# v4smd.net
KiCad netlist of a schematic drawn in EAGLE
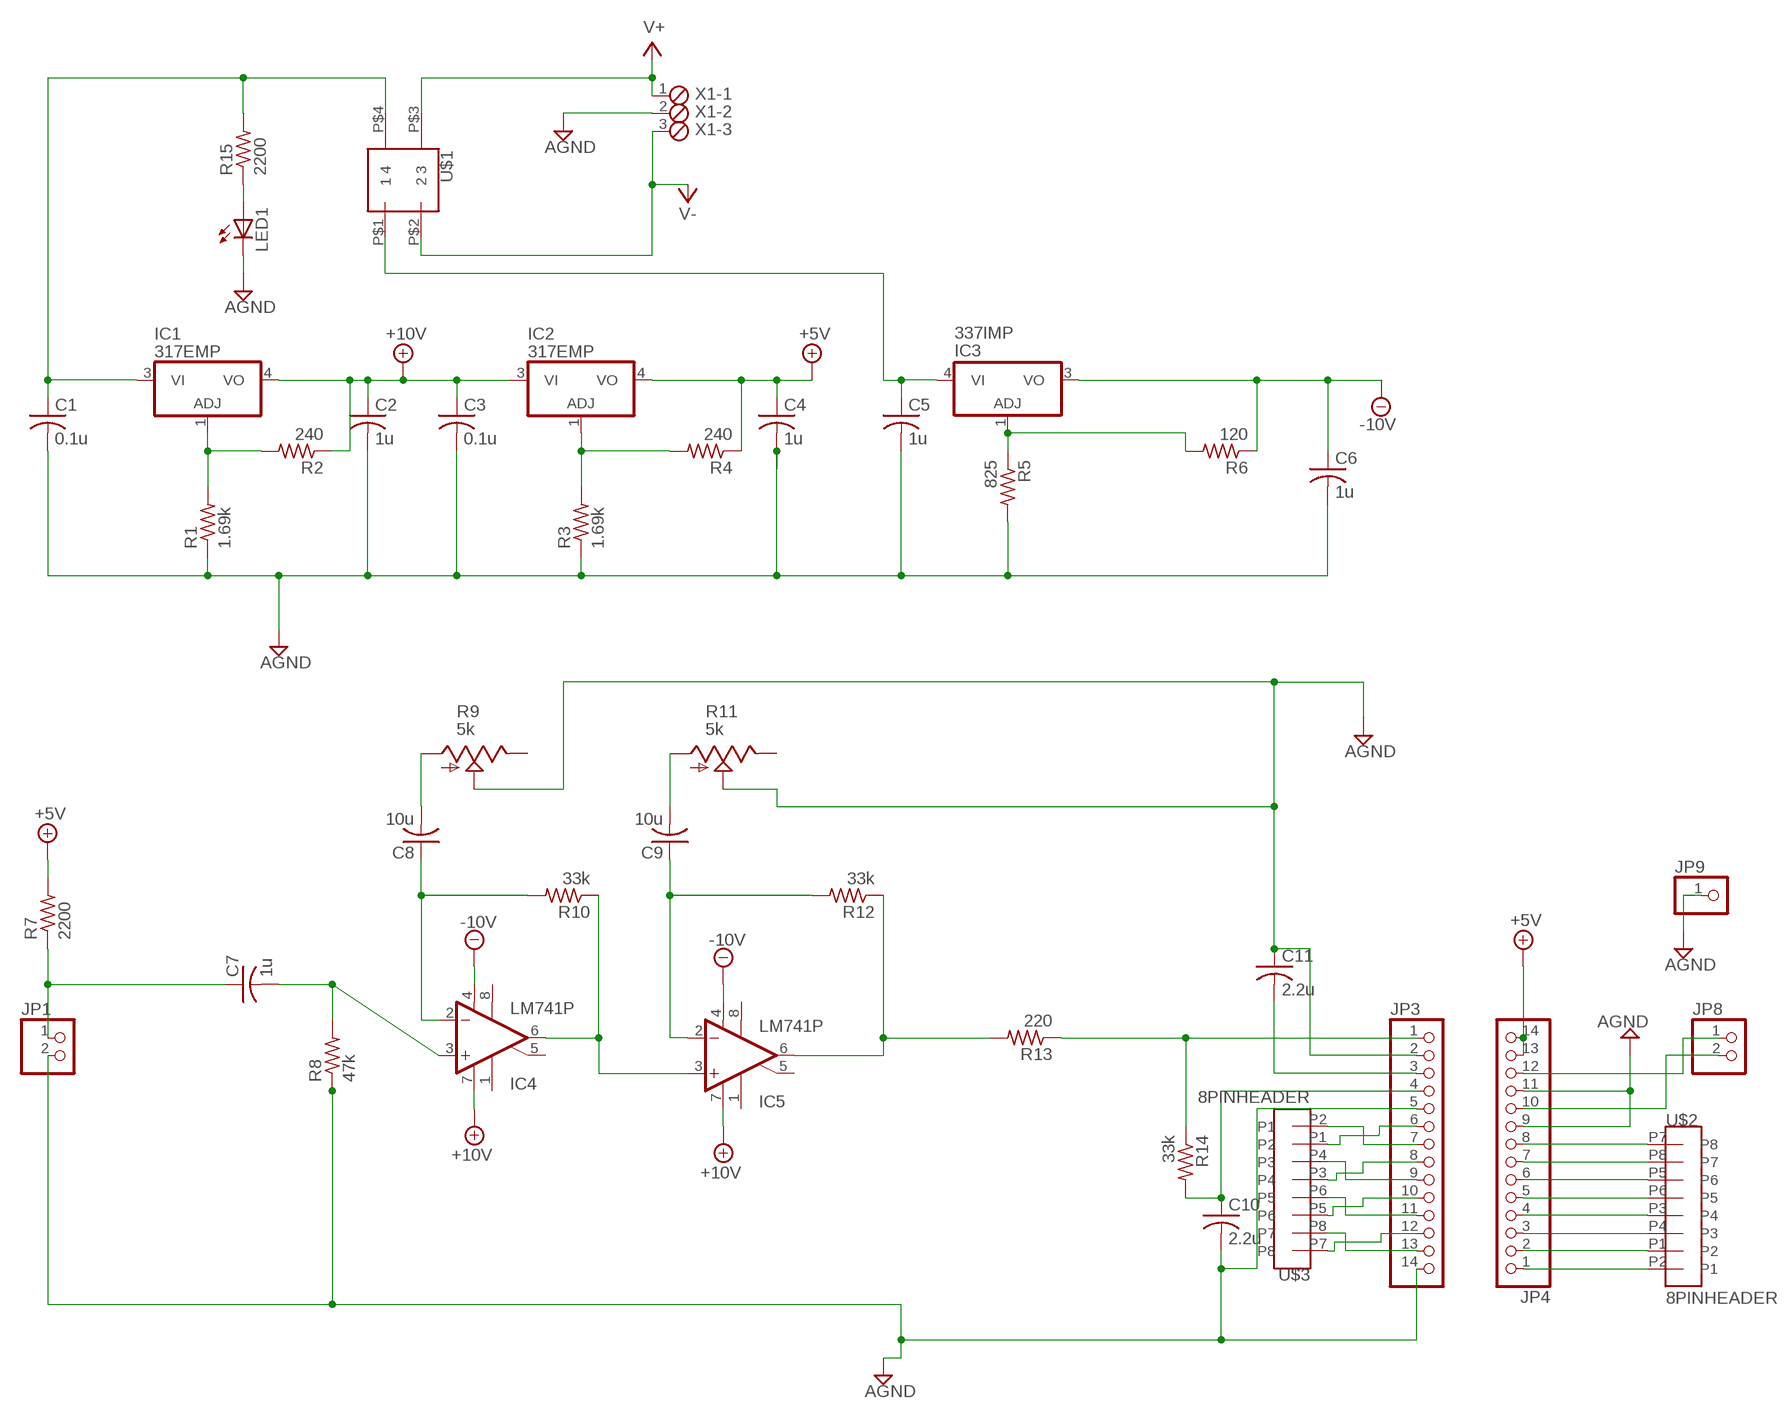
[diagram p0: schematic, sheet 1]

(export (version "E")
  (design (tool "Eeschema 10.0.6"))
  (components
    (comp (ref "C1")
      (value "0.1u")
      (footprint "eagle-import:C1206")
      (libsource (lib "eagle-import") (part "C-USC1206"))
    )
    (comp (ref "C2")
      (value "1u")
      (footprint "eagle-import:C1206")
      (libsource (lib "eagle-import") (part "C-USC1206"))
    )
    (comp (ref "C3")
      (value "0.1u")
      (footprint "eagle-import:C1206")
      (libsource (lib "eagle-import") (part "C-USC1206"))
    )
    (comp (ref "C4")
      (value "1u")
      (footprint "eagle-import:C1206")
      (libsource (lib "eagle-import") (part "C-USC1206"))
    )
    (comp (ref "C5")
      (value "1u")
      (footprint "eagle-import:C1206")
      (libsource (lib "eagle-import") (part "C-USC1206"))
    )
    (comp (ref "C6")
      (value "1u")
      (footprint "eagle-import:C1206")
      (libsource (lib "eagle-import") (part "C-USC1206"))
    )
    (comp (ref "C7")
      (value "1u")
      (footprint "eagle-import:C1206")
      (libsource (lib "eagle-import") (part "C-USC1206"))
    )
    (comp (ref "C8")
      (value "10u")
      (footprint "eagle-import:C1206")
      (libsource (lib "eagle-import") (part "C-USC1206"))
    )
    (comp (ref "C9")
      (value "10u")
      (footprint "eagle-import:C1206")
      (libsource (lib "eagle-import") (part "C-USC1206"))
    )
    (comp (ref "C10")
      (value "2.2u")
      (footprint "eagle-import:C1206")
      (libsource (lib "eagle-import") (part "C-USC1206"))
    )
    (comp (ref "C11")
      (value "2.2u")
      (footprint "eagle-import:C1206")
      (libsource (lib "eagle-import") (part "C-USC1206"))
    )
    (comp (ref "IC1")
      (value "317EMP")
      (footprint "eagle-import:SOT223")
      (libsource (lib "eagle-import") (part "317EMP"))
    )
    (comp (ref "IC2")
      (value "317EMP")
      (footprint "eagle-import:SOT223")
      (libsource (lib "eagle-import") (part "317EMP"))
    )
    (comp (ref "IC3")
      (value "337IMP")
      (footprint "eagle-import:SOT223")
      (libsource (lib "eagle-import") (part "337IMP"))
    )
    (comp (ref "IC4")
      (value "LM741P")
      (footprint "eagle-import:DIL08")
      (libsource (lib "eagle-import") (part "741PLM"))
    )
    (comp (ref "IC5")
      (value "LM741P")
      (footprint "eagle-import:DIL08")
      (libsource (lib "eagle-import") (part "741PLM"))
    )
    (comp (ref "JP1")
      (value "PINHD-1X2")
      (footprint "eagle-import:1X02")
      (libsource (lib "eagle-import") (part "PINHD-1X2"))
    )
    (comp (ref "JP3")
      (value "PINHD-1X14")
      (footprint "eagle-import:1X14")
      (libsource (lib "eagle-import") (part "PINHD-1X14"))
    )
    (comp (ref "JP4")
      (value "PINHD-1X14")
      (footprint "eagle-import:1X14")
      (libsource (lib "eagle-import") (part "PINHD-1X14"))
    )
    (comp (ref "JP8")
      (value "PINHD-1X2")
      (footprint "eagle-import:1X02")
      (libsource (lib "eagle-import") (part "PINHD-1X2"))
    )
    (comp (ref "JP9")
      (value "PINHD-1X1")
      (footprint "eagle-import:1X01")
      (libsource (lib "eagle-import") (part "PINHD-1X1"))
    )
    (comp (ref "LED1")
      (value "LED3MM")
      (footprint "eagle-import:LED3MM")
      (libsource (lib "eagle-import") (part "LED3MM"))
    )
    (comp (ref "R1")
      (value "1.69k")
      (footprint "eagle-import:R2512")
      (libsource (lib "eagle-import") (part "R-US_R2512"))
    )
    (comp (ref "R2")
      (value "240")
      (footprint "eagle-import:R2512")
      (libsource (lib "eagle-import") (part "R-US_R2512"))
    )
    (comp (ref "R3")
      (value "1.69k")
      (footprint "eagle-import:R2512")
      (libsource (lib "eagle-import") (part "R-US_R2512"))
    )
    (comp (ref "R4")
      (value "240")
      (footprint "eagle-import:R2512")
      (libsource (lib "eagle-import") (part "R-US_R2512"))
    )
    (comp (ref "R5")
      (value "825")
      (footprint "eagle-import:R2512")
      (libsource (lib "eagle-import") (part "R-US_R2512"))
    )
    (comp (ref "R6")
      (value "120")
      (footprint "eagle-import:R2512")
      (libsource (lib "eagle-import") (part "R-US_R2512"))
    )
    (comp (ref "R7")
      (value "2200")
      (footprint "eagle-import:R2512")
      (libsource (lib "eagle-import") (part "R-US_R2512"))
    )
    (comp (ref "R8")
      (value "47k")
      (footprint "eagle-import:R2512")
      (libsource (lib "eagle-import") (part "R-US_R2512"))
    )
    (comp (ref "R9")
      (value "5k")
      (footprint "eagle-import:B64Y")
      (libsource (lib "eagle-import") (part "TRIM_US-B64Y"))
    )
    (comp (ref "R10")
      (value "33k")
      (footprint "eagle-import:R2512")
      (libsource (lib "eagle-import") (part "R-US_R2512"))
    )
    (comp (ref "R11")
      (value "5k")
      (footprint "eagle-import:B64Y")
      (libsource (lib "eagle-import") (part "TRIM_US-B64Y"))
    )
    (comp (ref "R12")
      (value "33k")
      (footprint "eagle-import:R2512")
      (libsource (lib "eagle-import") (part "R-US_R2512"))
    )
    (comp (ref "R13")
      (value "220")
      (footprint "eagle-import:R2512")
      (libsource (lib "eagle-import") (part "R-US_R2512"))
    )
    (comp (ref "R14")
      (value "33k")
      (footprint "eagle-import:R2512")
      (libsource (lib "eagle-import") (part "R-US_R2512"))
    )
    (comp (ref "R15")
      (value "2200")
      (footprint "eagle-import:R2512")
      (libsource (lib "eagle-import") (part "R-US_R2512"))
    )
    (comp (ref "U$1")
      (value "S201031MS02Q")
      (footprint "eagle-import:DPST_FOOTPRINT")
      (libsource (lib "eagle-import") (part "S201031MS02Q"))
    )
    (comp (ref "U$2")
      (value "8PINHEADER")
      (footprint "eagle-import:2X4HEADER")
      (libsource (lib "eagle-import") (part "8PINHEADER"))
    )
    (comp (ref "U$3")
      (value "8PINHEADER")
      (footprint "eagle-import:2X4HEADER")
      (libsource (lib "eagle-import") (part "8PINHEADER"))
    )
    (comp (ref "X1")
      (value "MPT3")
      (footprint "eagle-import:3POL254")
      (libsource (lib "eagle-import") (part "MPT3"))
    )
  )
  (nets
    (net (code "1") (name "+5V") (class "Default")
      (node (ref "C4") (pin "1") (pinfunction "1_1") (pintype "passive"))
      (node (ref "IC2") (pin "4") (pinfunction "VO_4") (pintype "passive"))
      (node (ref "JP4") (pin "13") (pinfunction "13_13") (pintype "passive"))
      (node (ref "JP4") (pin "14") (pinfunction "14_14") (pintype "passive"))
      (node (ref "R4") (pin "1") (pinfunction "1_1") (pintype "passive"))
      (node (ref "R7") (pin "2") (pinfunction "2_2") (pintype "passive"))
    )
    (net (code "2") (name "+10V") (class "Default")
      (node (ref "C2") (pin "1") (pinfunction "1_1") (pintype "passive"))
      (node (ref "C3") (pin "1") (pinfunction "1_1") (pintype "passive"))
      (node (ref "IC1") (pin "4") (pinfunction "VO_4") (pintype "passive"))
      (node (ref "IC2") (pin "3") (pinfunction "VI_3") (pintype "input"))
      (node (ref "IC4") (pin "7") (pinfunction "V+_7") (pintype "power_in"))
      (node (ref "IC5") (pin "7") (pinfunction "V+_7") (pintype "power_in"))
      (node (ref "R2") (pin "1") (pinfunction "1_1") (pintype "passive"))
    )
    (net (code "3") (name "-10V") (class "Default")
      (node (ref "C6") (pin "1") (pinfunction "1_1") (pintype "passive"))
      (node (ref "IC3") (pin "3") (pinfunction "VO_3") (pintype "passive"))
      (node (ref "IC4") (pin "4") (pinfunction "V-_4") (pintype "power_in"))
      (node (ref "IC5") (pin "4") (pinfunction "V-_4") (pintype "power_in"))
      (node (ref "R6") (pin "1") (pinfunction "1_1") (pintype "passive"))
    )
    (net (code "4") (name "AGND") (class "Default")
      (node (ref "C1") (pin "2") (pinfunction "2_2") (pintype "passive"))
      (node (ref "C10") (pin "2") (pinfunction "2_2") (pintype "passive"))
      (node (ref "C11") (pin "1") (pinfunction "1_1") (pintype "passive"))
      (node (ref "C2") (pin "2") (pinfunction "2_2") (pintype "passive"))
      (node (ref "C3") (pin "2") (pinfunction "2_2") (pintype "passive"))
      (node (ref "C4") (pin "2") (pinfunction "2_2") (pintype "passive"))
      (node (ref "C5") (pin "2") (pinfunction "2_2") (pintype "passive"))
      (node (ref "C6") (pin "2") (pinfunction "2_2") (pintype "passive"))
      (node (ref "JP1") (pin "2") (pinfunction "2_2") (pintype "passive"))
      (node (ref "JP3") (pin "14") (pinfunction "14_14") (pintype "passive"))
      (node (ref "JP3") (pin "2") (pinfunction "2_2") (pintype "passive"))
      (node (ref "JP3") (pin "5") (pinfunction "5_5") (pintype "passive"))
      (node (ref "JP4") (pin "11") (pinfunction "11_11") (pintype "passive"))
      (node (ref "JP4") (pin "9") (pinfunction "9_9") (pintype "passive"))
      (node (ref "JP9") (pin "1") (pinfunction "1_1") (pintype "passive"))
      (node (ref "LED1") (pin "K") (pinfunction "C_K") (pintype "passive"))
      (node (ref "R1") (pin "1") (pinfunction "1_1") (pintype "passive"))
      (node (ref "R11") (pin "S") (pinfunction "S_S") (pintype "passive"))
      (node (ref "R3") (pin "1") (pinfunction "1_1") (pintype "passive"))
      (node (ref "R5") (pin "2") (pinfunction "2_2") (pintype "passive"))
      (node (ref "R8") (pin "1") (pinfunction "1_1") (pintype "passive"))
      (node (ref "R9") (pin "S") (pinfunction "S_S") (pintype "passive"))
      (node (ref "X1") (pin "2") (pinfunction "1_2") (pintype "passive"))
    )
    (net (code "5") (name "Net-(C7-Pad1)") (class "Default")
      (node (ref "C7") (pin "1") (pinfunction "1_1") (pintype "passive"))
      (node (ref "JP1") (pin "1") (pinfunction "1_1") (pintype "passive"))
      (node (ref "R7") (pin "1") (pinfunction "1_1") (pintype "passive"))
    )
    (net (code "6") (name "Net-(C8-Pad2)") (class "Default")
      (node (ref "C8") (pin "2") (pinfunction "2_2") (pintype "passive"))
      (node (ref "R9") (pin "A") (pinfunction "A_A") (pintype "passive"))
    )
    (net (code "7") (name "Net-(C9-Pad2)") (class "Default")
      (node (ref "C9") (pin "2") (pinfunction "2_2") (pintype "passive"))
      (node (ref "R11") (pin "A") (pinfunction "A_A") (pintype "passive"))
    )
    (net (code "8") (name "Net-(C10-Pad1)") (class "Default")
      (node (ref "C10") (pin "1") (pinfunction "1_1") (pintype "passive"))
      (node (ref "JP3") (pin "4") (pinfunction "4_4") (pintype "passive"))
      (node (ref "R14") (pin "2") (pinfunction "2_2") (pintype "passive"))
    )
    (net (code "9") (name "Net-(C11-Pad2)") (class "Default")
      (node (ref "C11") (pin "2") (pinfunction "2_2") (pintype "passive"))
      (node (ref "JP3") (pin "3") (pinfunction "3_3") (pintype "passive"))
    )
    (net (code "10") (name "Net-(IC1-ADJ)") (class "Default")
      (node (ref "IC1") (pin "1") (pinfunction "ADJ_1") (pintype "input"))
      (node (ref "R1") (pin "2") (pinfunction "2_2") (pintype "passive"))
      (node (ref "R2") (pin "2") (pinfunction "2_2") (pintype "passive"))
    )
    (net (code "11") (name "Net-(IC1-VI)") (class "Default")
      (node (ref "C1") (pin "1") (pinfunction "1_1") (pintype "passive"))
      (node (ref "IC1") (pin "3") (pinfunction "VI_3") (pintype "input"))
      (node (ref "R15") (pin "2") (pinfunction "2_2") (pintype "passive"))
      (node (ref "U$1") (pin "P$4") (pinfunction "4_P$4") (pintype "bidirectional"))
    )
    (net (code "12") (name "Net-(IC2-ADJ)") (class "Default")
      (node (ref "IC2") (pin "1") (pinfunction "ADJ_1") (pintype "input"))
      (node (ref "R3") (pin "2") (pinfunction "2_2") (pintype "passive"))
      (node (ref "R4") (pin "2") (pinfunction "2_2") (pintype "passive"))
    )
    (net (code "13") (name "Net-(IC3-ADJ)") (class "Default")
      (node (ref "IC3") (pin "1") (pinfunction "ADJ_1") (pintype "input"))
      (node (ref "R5") (pin "1") (pinfunction "1_1") (pintype "passive"))
      (node (ref "R6") (pin "2") (pinfunction "2_2") (pintype "passive"))
    )
    (net (code "14") (name "Net-(IC3-VI)") (class "Default")
      (node (ref "C5") (pin "1") (pinfunction "1_1") (pintype "passive"))
      (node (ref "IC3") (pin "4") (pinfunction "VI_4") (pintype "input"))
      (node (ref "U$1") (pin "P$1") (pinfunction "1_P$1") (pintype "bidirectional"))
    )
    (net (code "15") (name "Net-(IC4-+IN)") (class "Default")
      (node (ref "C7") (pin "2") (pinfunction "2_2") (pintype "passive"))
      (node (ref "IC4") (pin "3") (pinfunction "+IN_3") (pintype "input"))
      (node (ref "R8") (pin "2") (pinfunction "2_2") (pintype "passive"))
    )
    (net (code "16") (name "Net-(IC4--IN)") (class "Default")
      (node (ref "C8") (pin "1") (pinfunction "1_1") (pintype "passive"))
      (node (ref "IC4") (pin "2") (pinfunction "-IN_2") (pintype "input"))
      (node (ref "R10") (pin "2") (pinfunction "2_2") (pintype "passive"))
    )
    (net (code "17") (name "Net-(IC4-OUT)") (class "Default")
      (node (ref "IC4") (pin "6") (pinfunction "OUT_6") (pintype "output"))
      (node (ref "IC5") (pin "3") (pinfunction "+IN_3") (pintype "input"))
      (node (ref "R10") (pin "1") (pinfunction "1_1") (pintype "passive"))
    )
    (net (code "18") (name "Net-(IC5--IN)") (class "Default")
      (node (ref "C9") (pin "1") (pinfunction "1_1") (pintype "passive"))
      (node (ref "IC5") (pin "2") (pinfunction "-IN_2") (pintype "input"))
      (node (ref "R12") (pin "2") (pinfunction "2_2") (pintype "passive"))
    )
    (net (code "19") (name "Net-(IC5-OUT)") (class "Default")
      (node (ref "IC5") (pin "6") (pinfunction "OUT_6") (pintype "output"))
      (node (ref "R12") (pin "1") (pinfunction "1_1") (pintype "passive"))
      (node (ref "R13") (pin "2") (pinfunction "2_2") (pintype "passive"))
    )
    (net (code "20") (name "Net-(JP3-Pad1)") (class "Default")
      (node (ref "JP3") (pin "1") (pinfunction "1_1") (pintype "passive"))
      (node (ref "R13") (pin "1") (pinfunction "1_1") (pintype "passive"))
      (node (ref "R14") (pin "1") (pinfunction "1_1") (pintype "passive"))
    )
    (net (code "21") (name "Net-(JP4-Pad10)") (class "Default")
      (node (ref "JP4") (pin "10") (pinfunction "10_10") (pintype "passive"))
      (node (ref "JP8") (pin "2") (pinfunction "2_2") (pintype "passive"))
    )
    (net (code "22") (name "Net-(JP4-Pad12)") (class "Default")
      (node (ref "JP4") (pin "12") (pinfunction "12_12") (pintype "passive"))
      (node (ref "JP8") (pin "1") (pinfunction "1_1") (pintype "passive"))
    )
    (net (code "23") (name "Net-(LED1-PadA)") (class "Default")
      (node (ref "LED1") (pin "A") (pinfunction "A_A") (pintype "passive"))
      (node (ref "R15") (pin "1") (pinfunction "1_1") (pintype "passive"))
    )
    (net (code "24") (name "Net-(U$2-P1)") (class "Default")
      (node (ref "JP4") (pin "1") (pinfunction "1_1") (pintype "passive"))
      (node (ref "U$2") (pin "P2") (pinfunction "P1_P2") (pintype "bidirectional"))
    )
    (net (code "25") (name "Net-(U$2-P2)") (class "Default")
      (node (ref "JP4") (pin "2") (pinfunction "2_2") (pintype "passive"))
      (node (ref "U$2") (pin "P1") (pinfunction "P2_P1") (pintype "bidirectional"))
    )
    (net (code "26") (name "Net-(U$2-P3)") (class "Default")
      (node (ref "JP4") (pin "3") (pinfunction "3_3") (pintype "passive"))
      (node (ref "U$2") (pin "P4") (pinfunction "P3_P4") (pintype "bidirectional"))
    )
    (net (code "27") (name "Net-(U$2-P4)") (class "Default")
      (node (ref "JP4") (pin "4") (pinfunction "4_4") (pintype "passive"))
      (node (ref "U$2") (pin "P3") (pinfunction "P4_P3") (pintype "bidirectional"))
    )
    (net (code "28") (name "Net-(U$2-P5)") (class "Default")
      (node (ref "JP4") (pin "5") (pinfunction "5_5") (pintype "passive"))
      (node (ref "U$2") (pin "P6") (pinfunction "P5_P6") (pintype "bidirectional"))
    )
    (net (code "29") (name "Net-(U$2-P6)") (class "Default")
      (node (ref "JP4") (pin "6") (pinfunction "6_6") (pintype "passive"))
      (node (ref "U$2") (pin "P5") (pinfunction "P6_P5") (pintype "bidirectional"))
    )
    (net (code "30") (name "Net-(U$2-P7)") (class "Default")
      (node (ref "JP4") (pin "7") (pinfunction "7_7") (pintype "passive"))
      (node (ref "U$2") (pin "P8") (pinfunction "P7_P8") (pintype "bidirectional"))
    )
    (net (code "31") (name "Net-(U$2-P8)") (class "Default")
      (node (ref "JP4") (pin "8") (pinfunction "8_8") (pintype "passive"))
      (node (ref "U$2") (pin "P7") (pinfunction "P8_P7") (pintype "bidirectional"))
    )
    (net (code "32") (name "Net-(U$3-P1)") (class "Default")
      (node (ref "JP3") (pin "7") (pinfunction "7_7") (pintype "passive"))
      (node (ref "U$3") (pin "P2") (pinfunction "P1_P2") (pintype "bidirectional"))
    )
    (net (code "33") (name "Net-(U$3-P2)") (class "Default")
      (node (ref "JP3") (pin "6") (pinfunction "6_6") (pintype "passive"))
      (node (ref "U$3") (pin "P1") (pinfunction "P2_P1") (pintype "bidirectional"))
    )
    (net (code "34") (name "Net-(U$3-P3)") (class "Default")
      (node (ref "JP3") (pin "9") (pinfunction "9_9") (pintype "passive"))
      (node (ref "U$3") (pin "P4") (pinfunction "P3_P4") (pintype "bidirectional"))
    )
    (net (code "35") (name "Net-(U$3-P4)") (class "Default")
      (node (ref "JP3") (pin "8") (pinfunction "8_8") (pintype "passive"))
      (node (ref "U$3") (pin "P3") (pinfunction "P4_P3") (pintype "bidirectional"))
    )
    (net (code "36") (name "Net-(U$3-P5)") (class "Default")
      (node (ref "JP3") (pin "11") (pinfunction "11_11") (pintype "passive"))
      (node (ref "U$3") (pin "P6") (pinfunction "P5_P6") (pintype "bidirectional"))
    )
    (net (code "37") (name "Net-(U$3-P6)") (class "Default")
      (node (ref "JP3") (pin "10") (pinfunction "10_10") (pintype "passive"))
      (node (ref "U$3") (pin "P5") (pinfunction "P6_P5") (pintype "bidirectional"))
    )
    (net (code "38") (name "Net-(U$3-P7)") (class "Default")
      (node (ref "JP3") (pin "13") (pinfunction "13_13") (pintype "passive"))
      (node (ref "U$3") (pin "P8") (pinfunction "P7_P8") (pintype "bidirectional"))
    )
    (net (code "39") (name "Net-(U$3-P8)") (class "Default")
      (node (ref "JP3") (pin "12") (pinfunction "12_12") (pintype "passive"))
      (node (ref "U$3") (pin "P7") (pinfunction "P8_P7") (pintype "bidirectional"))
    )
    (net (code "40") (name "V+") (class "Default")
      (node (ref "U$1") (pin "P$3") (pinfunction "3_P$3") (pintype "bidirectional"))
      (node (ref "X1") (pin "1") (pinfunction "1_1") (pintype "passive"))
    )
    (net (code "41") (name "V-") (class "Default")
      (node (ref "U$1") (pin "P$2") (pinfunction "2_P$2") (pintype "bidirectional"))
      (node (ref "X1") (pin "3") (pinfunction "1_3") (pintype "passive"))
    )
    (net (code "42") (name "unconnected-(IC4-ON1-Pad1)") (class "Default")
      (node (ref "IC4") (pin "1") (pinfunction "ON1_1") (pintype "passive"))
    )
    (net (code "43") (name "unconnected-(IC4-ON2-Pad5)") (class "Default")
      (node (ref "IC4") (pin "5") (pinfunction "ON2_5") (pintype "passive"))
    )
    (net (code "44") (name "unconnected-(IC4-OPT-Pad8)") (class "Default")
      (node (ref "IC4") (pin "8") (pinfunction "OPT_8") (pintype "passive"))
    )
    (net (code "45") (name "unconnected-(IC5-ON1-Pad1)") (class "Default")
      (node (ref "IC5") (pin "1") (pinfunction "ON1_1") (pintype "passive"))
    )
    (net (code "46") (name "unconnected-(IC5-ON2-Pad5)") (class "Default")
      (node (ref "IC5") (pin "5") (pinfunction "ON2_5") (pintype "passive"))
    )
    (net (code "47") (name "unconnected-(IC5-OPT-Pad8)") (class "Default")
      (node (ref "IC5") (pin "8") (pinfunction "OPT_8") (pintype "passive"))
    )
    (net (code "48") (name "unconnected-(R9-PadE)") (class "Default")
      (node (ref "R9") (pin "E") (pinfunction "E_E") (pintype "passive"))
    )
    (net (code "49") (name "unconnected-(R11-PadE)") (class "Default")
      (node (ref "R11") (pin "E") (pinfunction "E_E") (pintype "passive"))
    )
  )
)
